# design.net
KiCad netlist of a schematic drawn in EasyEDA Pro
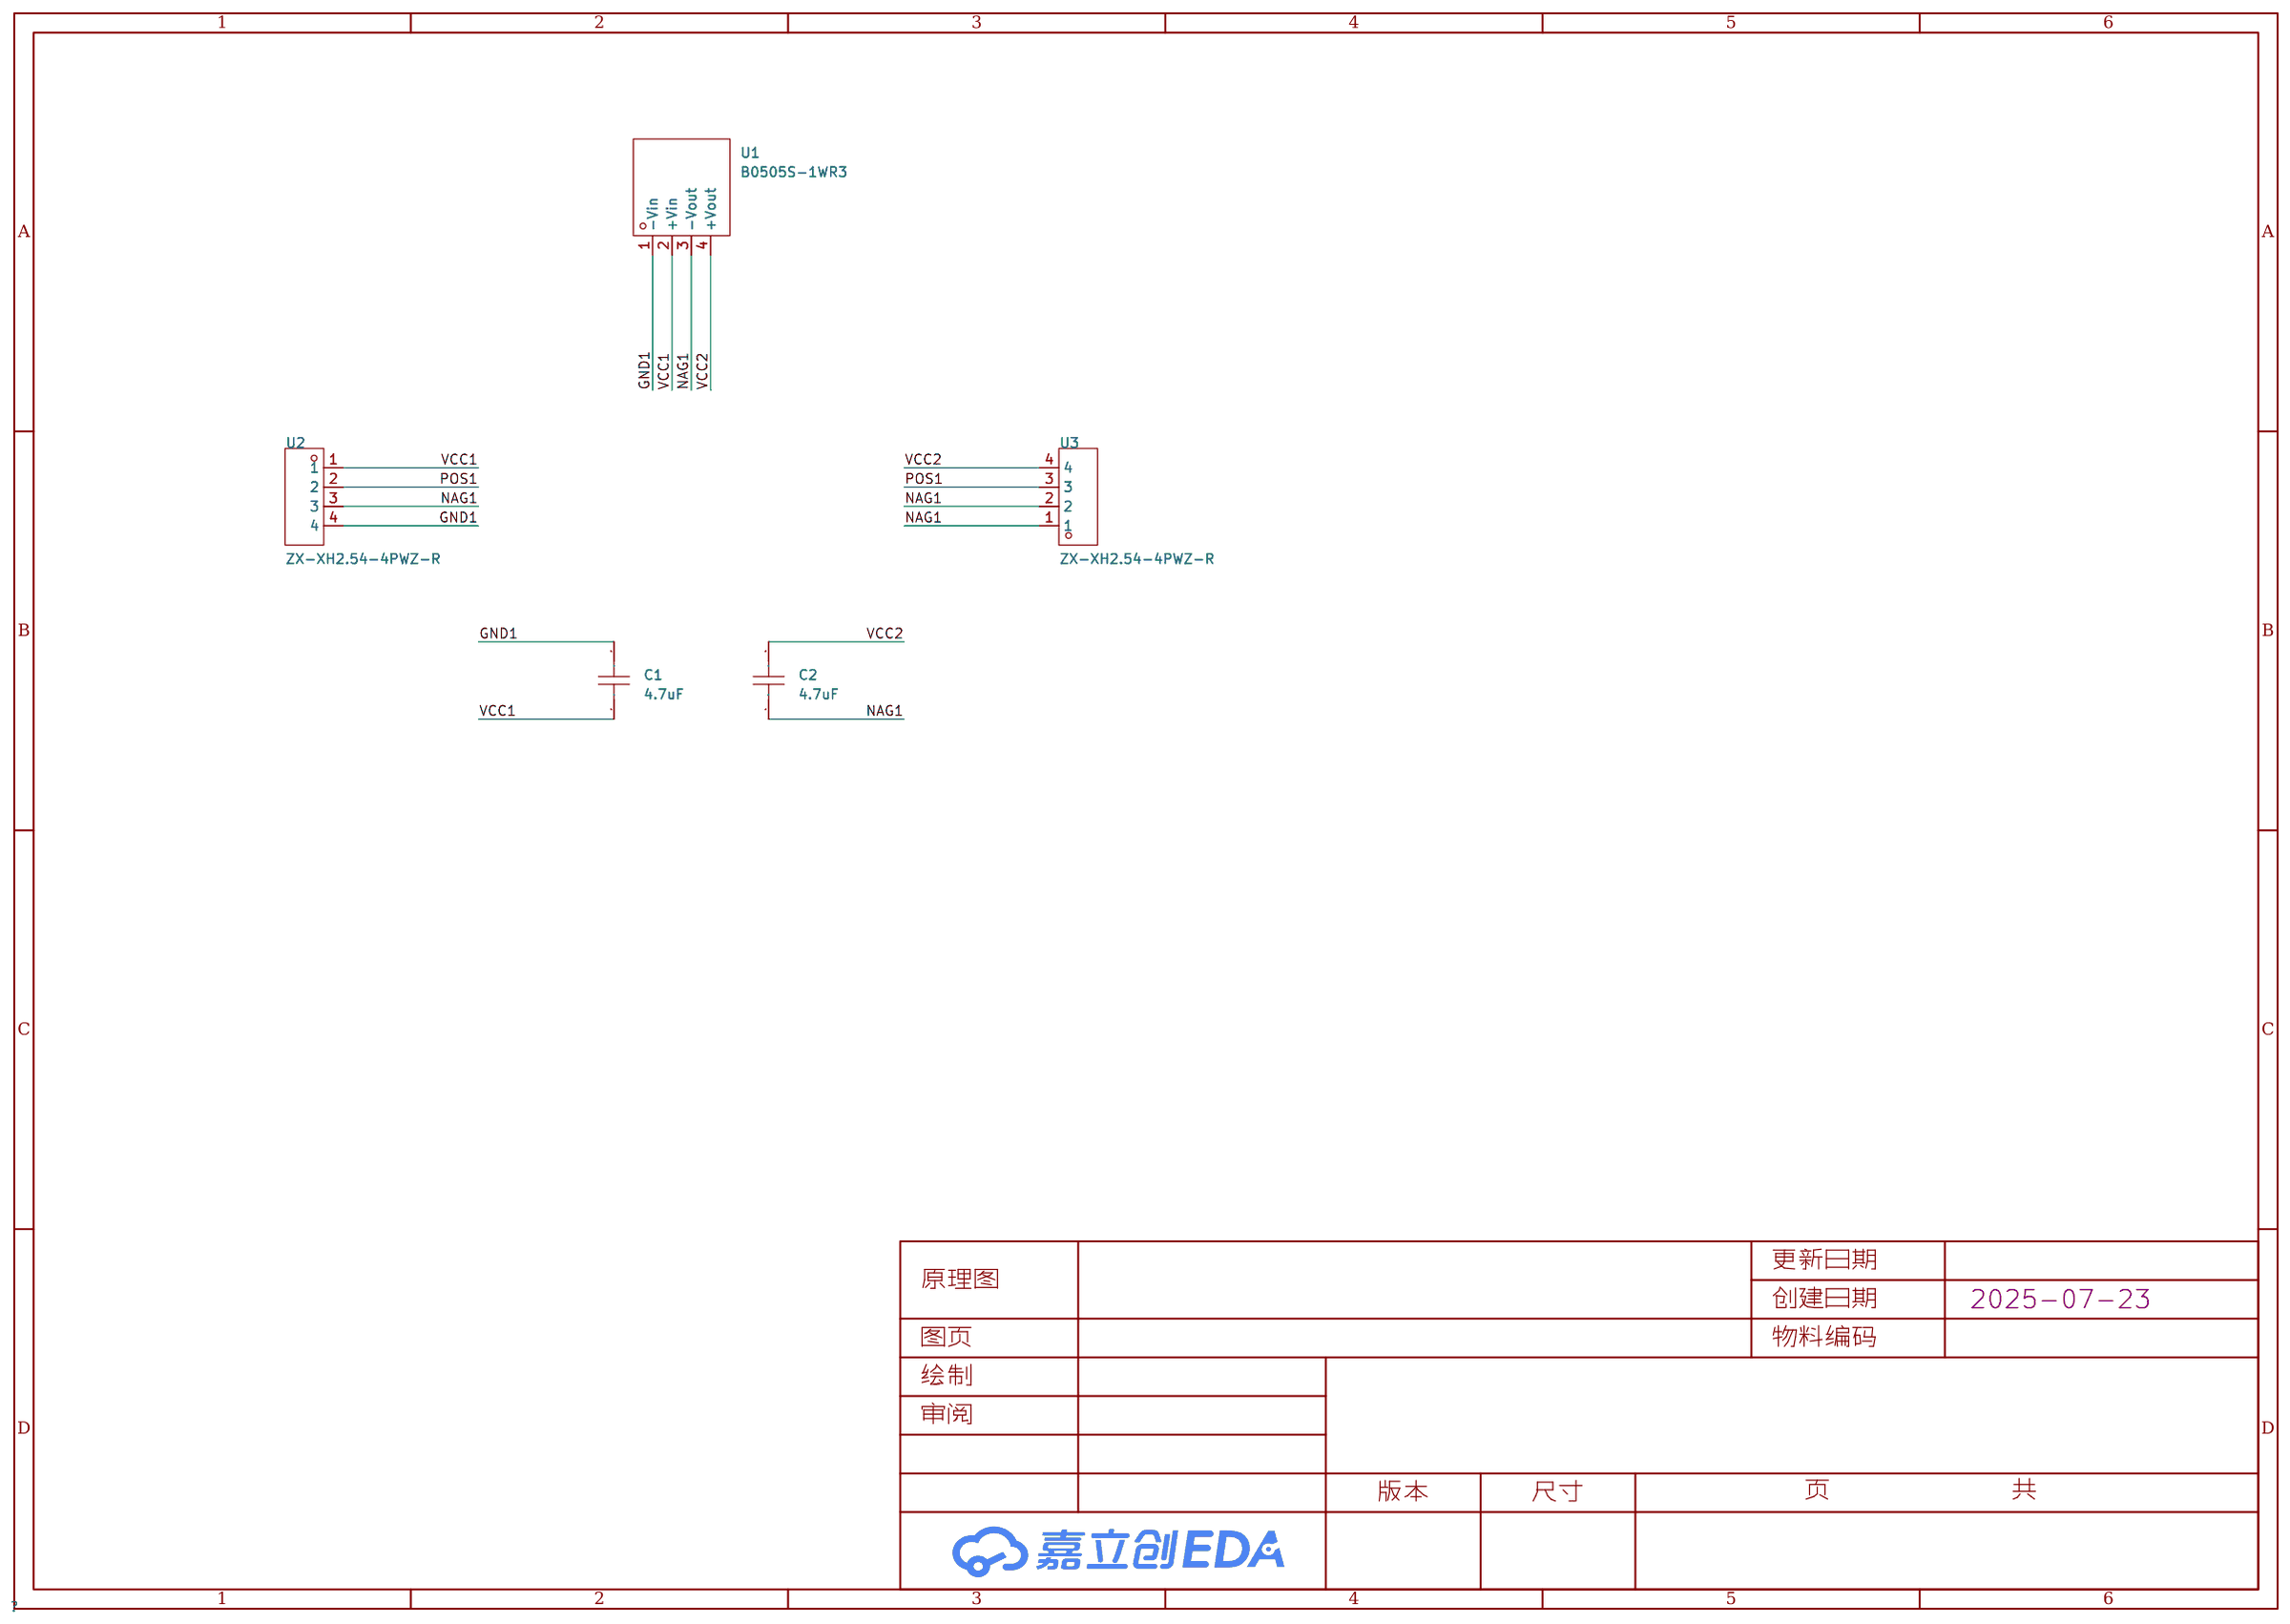
[diagram p0: schematic sheet]

(export (version "E")
  (design (tool "Eeschema 10.0.6"))
  (components
    (comp (ref "C1")
      (value "4.7uF")
      (footprint "easyedapro:C1206")
      (description "容值:4.7uF;精度:±10%;额定电压:100V;材质(温度系数):X7S;")
      (fields
        (field (name "Manufacturer Part") "GRM31CC72A475KE11L")
        (field (name "Manufacturer") "muRata(村田)")
      )
      (libsource (lib "easyedapro") (part "GRM31CC72A475KE11L"))
    )
    (comp (ref "C2")
      (value "4.7uF")
      (footprint "easyedapro:C1206")
      (description "容值:4.7uF;精度:±10%;额定电压:100V;材质(温度系数):X7S;")
      (fields
        (field (name "Manufacturer Part") "GRM31CC72A475KE11L")
        (field (name "Manufacturer") "muRata(村田)")
      )
      (libsource (lib "easyedapro") (part "GRM31CC72A475KE11L"))
    )
    (comp (ref "U1")
      (value "B0505S-1WR3")
      (footprint "easyedapro:PWRM-TH_B0505S-1WR3")
      (fields (field (name "Manufacturer") "EVISUN(易成)"))
      (libsource (lib "easyedapro") (part "B0505S-1WR3_C7465178"))
    )
    (comp (ref "U2")
      (value "ZX-XH2.54-4PWZ-R")
      (footprint "easyedapro:CONN-TH_4P-P2.50_ZX-XH2.54-4PWZ-Y")
      (fields (field (name "Manufacturer") "Megastar(兆星)"))
      (libsource (lib "easyedapro") (part "ZX-XH2.54-4PWZ-R"))
    )
    (comp (ref "U3")
      (value "ZX-XH2.54-4PWZ-R")
      (footprint "easyedapro:CONN-TH_4P-P2.50_ZX-XH2.54-4PWZ-Y")
      (fields (field (name "Manufacturer") "Megastar(兆星)"))
      (libsource (lib "easyedapro") (part "ZX-XH2.54-4PWZ-R"))
    )
  )
  (nets
    (net (code "1") (name "/GND1") (class "Default")
      (node (ref "C1") (pin "2") (pinfunction "2_2") (pintype "unspecified"))
      (node (ref "U1") (pin "1") (pinfunction "-Vin_1") (pintype "unspecified"))
      (node (ref "U2") (pin "4") (pinfunction "4_4") (pintype "unspecified"))
    )
    (net (code "2") (name "/NAG1") (class "Default")
      (node (ref "C2") (pin "1") (pinfunction "1_1") (pintype "unspecified"))
      (node (ref "U1") (pin "3") (pinfunction "-Vout_3") (pintype "unspecified"))
      (node (ref "U2") (pin "3") (pinfunction "3_3") (pintype "unspecified"))
      (node (ref "U3") (pin "1") (pinfunction "1_1") (pintype "unspecified"))
      (node (ref "U3") (pin "2") (pinfunction "2_2") (pintype "unspecified"))
    )
    (net (code "3") (name "/POS1") (class "Default")
      (node (ref "U2") (pin "2") (pinfunction "2_2") (pintype "unspecified"))
      (node (ref "U3") (pin "3") (pinfunction "3_3") (pintype "unspecified"))
    )
    (net (code "4") (name "/VCC1") (class "Default")
      (node (ref "C1") (pin "1") (pinfunction "1_1") (pintype "unspecified"))
      (node (ref "U1") (pin "2") (pinfunction "+Vin_2") (pintype "unspecified"))
      (node (ref "U2") (pin "1") (pinfunction "1_1") (pintype "unspecified"))
    )
    (net (code "5") (name "/VCC2") (class "Default")
      (node (ref "C2") (pin "2") (pinfunction "2_2") (pintype "unspecified"))
      (node (ref "U1") (pin "4") (pinfunction "+Vout_4") (pintype "unspecified"))
      (node (ref "U3") (pin "4") (pinfunction "4_4") (pintype "unspecified"))
    )
  )
)
